# source_eagle.net
KiCad netlist of a schematic drawn in EAGLE
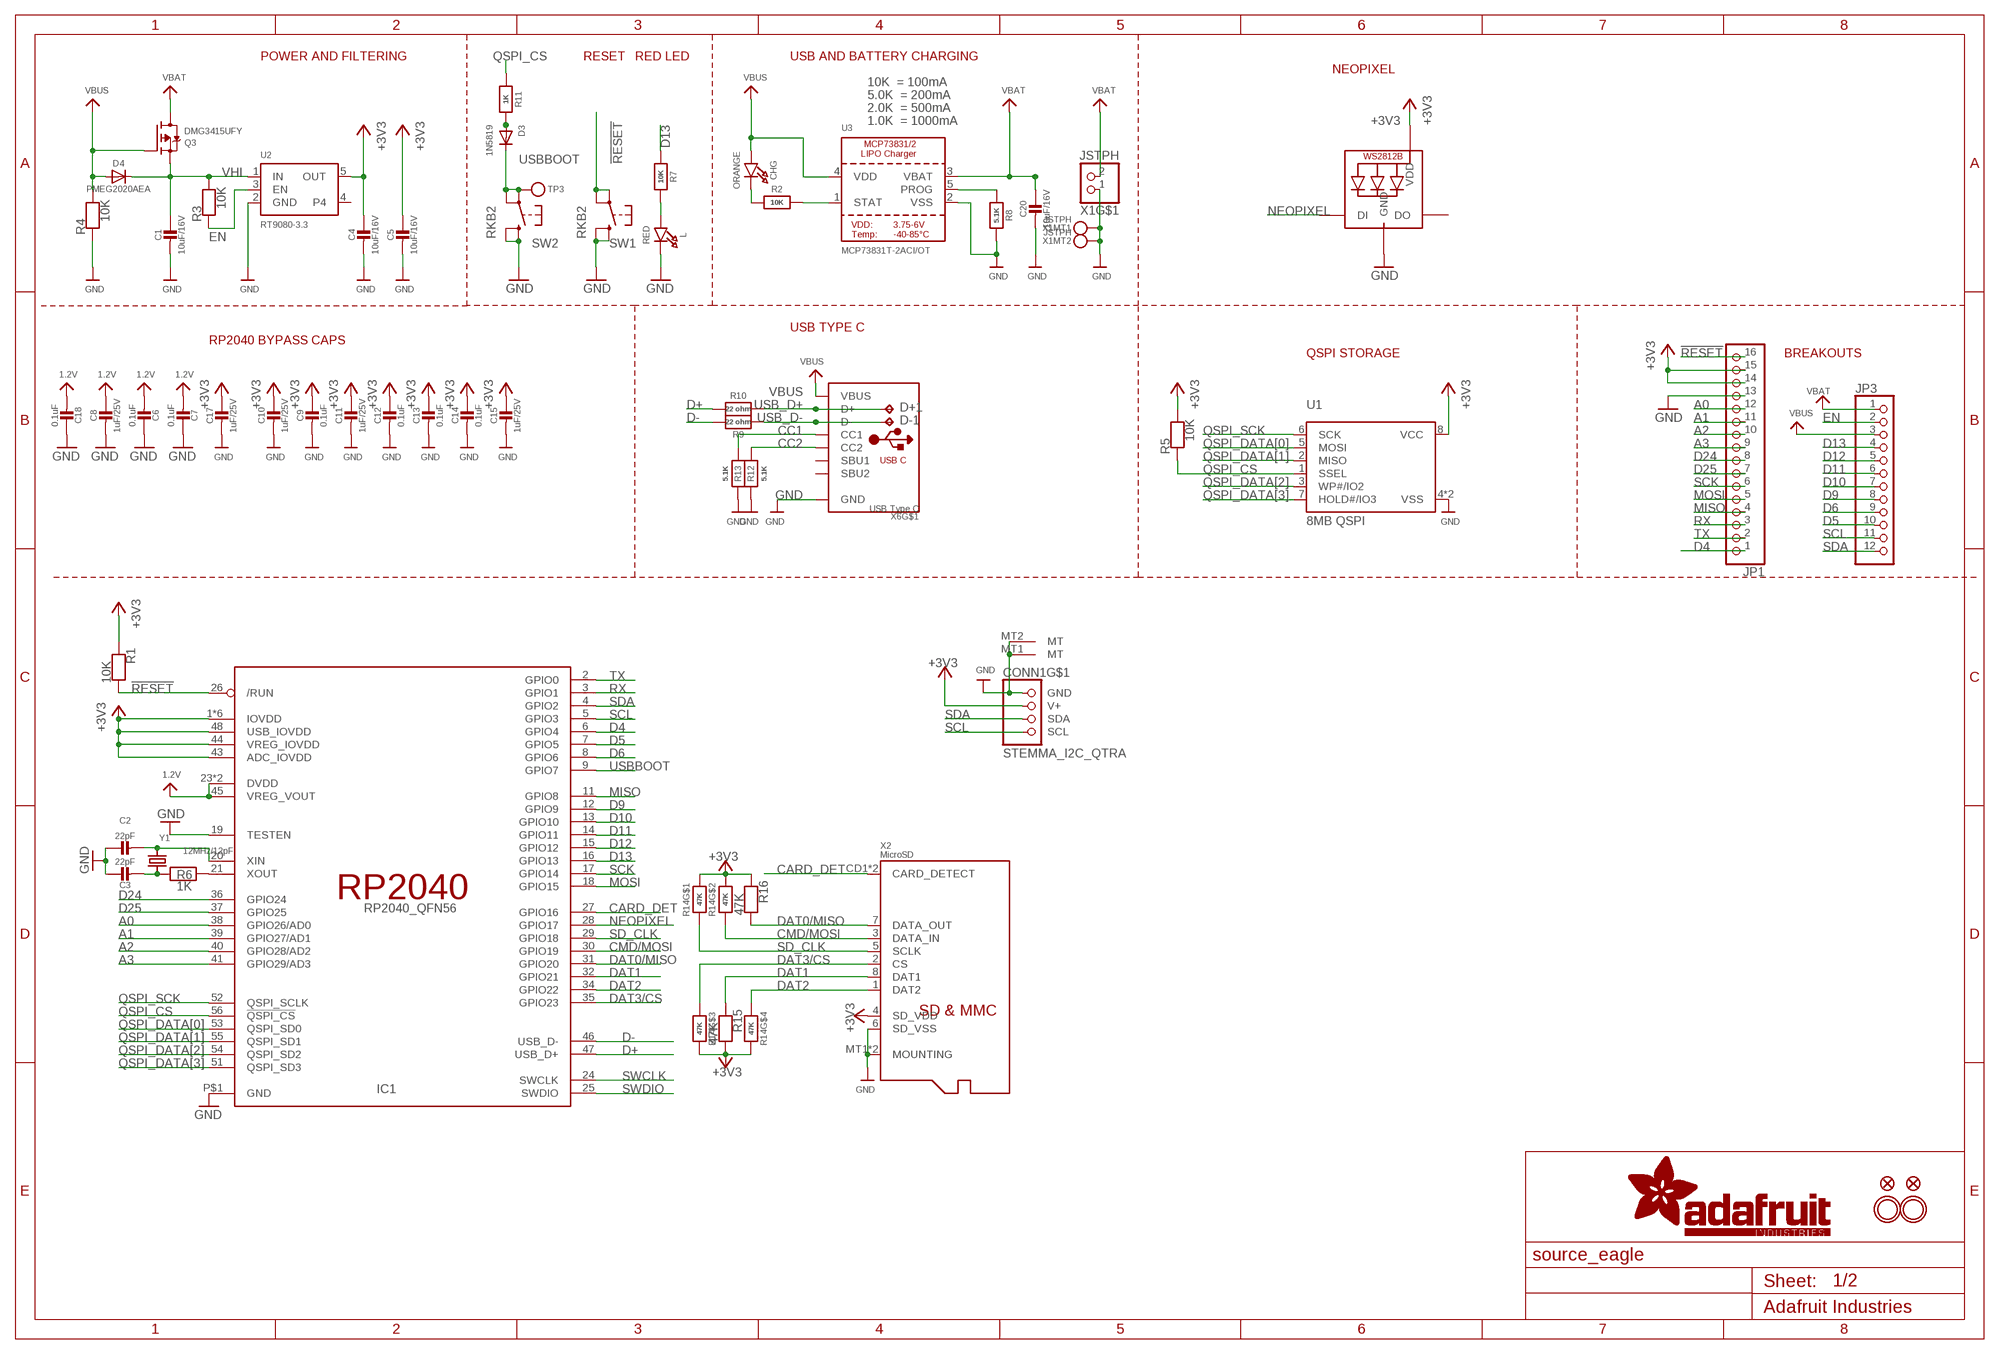
[diagram p0: schematic, sheet 1]

(export (version "E")
  (design (tool "Eeschema 10.0.6"))
  (components
    (comp (ref "C1")
      (value "10uF/16V")
      (footprint "eagle-import:0805-NO")
      (libsource (lib "eagle-import") (part "CAP_CERAMIC0805-NOOUTLINE"))
    )
    (comp (ref "C2")
      (value "22pF")
      (footprint "eagle-import:_0402NO")
      (libsource (lib "eagle-import") (part "CAP_CERAMIC_0402NO"))
    )
    (comp (ref "C3")
      (value "22pF")
      (footprint "eagle-import:_0402NO")
      (libsource (lib "eagle-import") (part "CAP_CERAMIC_0402NO"))
    )
    (comp (ref "C4")
      (value "10uF/16V")
      (footprint "eagle-import:0805-NO")
      (fields (field (name "REV") "A"))
      (libsource (lib "eagle-import") (part "CAP_CERAMIC0805-NOOUTLINE"))
    )
    (comp (ref "C5")
      (value "10uF/16V")
      (footprint "eagle-import:0805-NO")
      (libsource (lib "eagle-import") (part "CAP_CERAMIC0805-NOOUTLINE"))
    )
    (comp (ref "C6")
      (value "0.1uF")
      (footprint "eagle-import:_0402NO")
      (libsource (lib "eagle-import") (part "CAP_CERAMIC_0402NO"))
    )
    (comp (ref "C7")
      (value "0.1uF")
      (footprint "eagle-import:_0402NO")
      (libsource (lib "eagle-import") (part "CAP_CERAMIC_0402NO"))
    )
    (comp (ref "C8")
      (value "1uF/25V")
      (footprint "eagle-import:_0402NO")
      (libsource (lib "eagle-import") (part "CAP_CERAMIC_0402NO"))
    )
    (comp (ref "C9")
      (value "0.1uF")
      (footprint "eagle-import:_0402NO")
      (libsource (lib "eagle-import") (part "CAP_CERAMIC_0402NO"))
    )
    (comp (ref "C10")
      (value "1uF/25V")
      (footprint "eagle-import:_0402NO")
      (libsource (lib "eagle-import") (part "CAP_CERAMIC_0402NO"))
    )
    (comp (ref "C11")
      (value "1uF/25V")
      (footprint "eagle-import:_0402NO")
      (libsource (lib "eagle-import") (part "CAP_CERAMIC_0402NO"))
    )
    (comp (ref "C12")
      (value "0.1uF")
      (footprint "eagle-import:_0402NO")
      (libsource (lib "eagle-import") (part "CAP_CERAMIC_0402NO"))
    )
    (comp (ref "C13")
      (value "0.1uF")
      (footprint "eagle-import:_0402NO")
      (libsource (lib "eagle-import") (part "CAP_CERAMIC_0402NO"))
    )
    (comp (ref "C14")
      (value "0.1uF")
      (footprint "eagle-import:_0402NO")
      (libsource (lib "eagle-import") (part "CAP_CERAMIC_0402NO"))
    )
    (comp (ref "C15")
      (value "1uF/25V")
      (footprint "eagle-import:_0402NO")
      (libsource (lib "eagle-import") (part "CAP_CERAMIC_0402NO"))
    )
    (comp (ref "C17")
      (value "1uF/25V")
      (footprint "eagle-import:_0402NO")
      (libsource (lib "eagle-import") (part "CAP_CERAMIC_0402NO"))
    )
    (comp (ref "C18")
      (value "0.1uF")
      (footprint "eagle-import:_0402NO")
      (libsource (lib "eagle-import") (part "CAP_CERAMIC_0402NO"))
    )
    (comp (ref "C20")
      (value "10uF/16V")
      (footprint "eagle-import:0805-NO")
      (libsource (lib "eagle-import") (part "CAP_CERAMIC0805-NOOUTLINE"))
    )
    (comp (ref "CHG")
      (value "ORANGE")
      (footprint "eagle-import:CHIPLED_0603_NOOUTLINE")
      (libsource (lib "eagle-import") (part "LED0603_NOOUTLINE"))
    )
    (comp (ref "CONN1")
      (value "STEMMA_I2C_QTRA")
      (footprint "eagle-import:JST_SH4_RA")
      (libsource (lib "eagle-import") (part "STEMMA_I2C_QTRA"))
    )
    (comp (ref "D+1")
      (value "TPB1,27")
      (footprint "eagle-import:B1,27")
      (libsource (lib "eagle-import") (part "TPB1,27"))
    )
    (comp (ref "D-1")
      (value "TPB1,27")
      (footprint "eagle-import:B1,27")
      (libsource (lib "eagle-import") (part "TPB1,27"))
    )
    (comp (ref "D3")
      (value "1N5819")
      (footprint "eagle-import:SOD-323_MINI")
      (libsource (lib "eagle-import") (part "DIODE_SOD323MINI"))
    )
    (comp (ref "D4")
      (value "PMEG2020AEA")
      (footprint "eagle-import:SOD-323F")
      (libsource (lib "eagle-import") (part "DIODESOD-323F"))
    )
    (comp (ref "IC1")
      (value "RP2040_QFN56")
      (footprint "eagle-import:QFN56_7MM_REDUCEDEPAD")
      (libsource (lib "eagle-import") (part "RP2040_QFN56"))
    )
    (comp (ref "JP1")
      (value "HEADER-1X16ROUND")
      (footprint "eagle-import:1X16_ROUND")
      (libsource (lib "eagle-import") (part "HEADER-1X16ROUND"))
    )
    (comp (ref "JP3")
      (value "HEADER-1X12")
      (footprint "eagle-import:1X12_ROUND")
      (libsource (lib "eagle-import") (part "HEADER-1X12"))
    )
    (comp (ref "L")
      (value "RED")
      (footprint "eagle-import:CHIPLED_0603_NOOUTLINE")
      (libsource (lib "eagle-import") (part "LED0603_NOOUTLINE"))
    )
    (comp (ref "LED1")
      (value "WS2812B_SK6805_1515")
      (footprint "eagle-import:SK6805_1515")
      (libsource (lib "eagle-import") (part "WS2812B_SK6805_1515"))
    )
    (comp (ref "Q3")
      (value "DMG3415UFY")
      (footprint "eagle-import:DFN2015-3")
      (libsource (lib "eagle-import") (part "MOSFET-P_DFN2015"))
    )
    (comp (ref "R1")
      (value "10K")
      (footprint "eagle-import:_0402NO")
      (libsource (lib "eagle-import") (part "RESISTOR_0402NO"))
    )
    (comp (ref "R2")
      (value "10K")
      (footprint "eagle-import:_0402NO")
      (libsource (lib "eagle-import") (part "RESISTOR_0402NO"))
    )
    (comp (ref "R3")
      (value "10K")
      (footprint "eagle-import:_0402NO")
      (libsource (lib "eagle-import") (part "RESISTOR_0402NO"))
    )
    (comp (ref "R4")
      (value "10K")
      (footprint "eagle-import:_0402NO")
      (libsource (lib "eagle-import") (part "RESISTOR_0402NO"))
    )
    (comp (ref "R5")
      (value "10K")
      (footprint "eagle-import:_0402NO")
      (libsource (lib "eagle-import") (part "RESISTOR_0402NO"))
    )
    (comp (ref "R6")
      (value "1K")
      (footprint "eagle-import:_0402NO")
      (libsource (lib "eagle-import") (part "RESISTOR_0402NO"))
    )
    (comp (ref "R7")
      (value "10K")
      (footprint "eagle-import:_0402NO")
      (libsource (lib "eagle-import") (part "RESISTOR_0402NO"))
    )
    (comp (ref "R8")
      (value "5.1K")
      (footprint "eagle-import:_0402NO")
      (libsource (lib "eagle-import") (part "RESISTOR_0402NO"))
    )
    (comp (ref "R9")
      (value "22 ohm")
      (footprint "eagle-import:_0402NO")
      (libsource (lib "eagle-import") (part "RESISTOR_0402NO"))
    )
    (comp (ref "R10")
      (value "22 ohm")
      (footprint "eagle-import:_0402NO")
      (libsource (lib "eagle-import") (part "RESISTOR_0402NO"))
    )
    (comp (ref "R11")
      (value "1K")
      (footprint "eagle-import:_0402NO")
      (libsource (lib "eagle-import") (part "RESISTOR_0402NO"))
    )
    (comp (ref "R12")
      (value "5.1K")
      (footprint "eagle-import:_0402NO")
      (libsource (lib "eagle-import") (part "RESISTOR_0402NO"))
    )
    (comp (ref "R13")
      (value "5.1K")
      (footprint "eagle-import:_0402NO")
      (libsource (lib "eagle-import") (part "RESISTOR_0402NO"))
    )
    (comp (ref "R14")
      (value "47K")
      (footprint "eagle-import:RESPACK_4X0603")
      (libsource (lib "eagle-import") (part "RESISTOR_4PACK"))
    )
    (comp (ref "R15")
      (value "47K")
      (footprint "eagle-import:_0402NO")
      (libsource (lib "eagle-import") (part "RESISTOR_0402NO"))
    )
    (comp (ref "R16")
      (value "47K")
      (footprint "eagle-import:_0402NO")
      (libsource (lib "eagle-import") (part "RESISTOR_0402NO"))
    )
    (comp (ref "SW1")
      (value "RKB2")
      (footprint "eagle-import:BTN_RKB2_4.6X2.8")
      (libsource (lib "eagle-import") (part "SWITCH_TACT_SMT_RKB2"))
    )
    (comp (ref "SW2")
      (value "RKB2")
      (footprint "eagle-import:BTN_RKB2_4.6X2.8")
      (libsource (lib "eagle-import") (part "SWITCH_TACT_SMT_RKB2"))
    )
    (comp (ref "TP3")
      (value "TESTPOINTROUND1.5MMNO")
      (footprint "eagle-import:TESTPOINT_ROUND_1.5MM_NO")
      (libsource (lib "eagle-import") (part "TESTPOINTROUND1.5MMNO"))
    )
    (comp (ref "U$31")
      (value "MOUNTINGHOLE2.5")
      (footprint "eagle-import:MOUNTINGHOLE_2.5_PLATED")
      (libsource (lib "eagle-import") (part "MOUNTINGHOLE2.5"))
    )
    (comp (ref "U$32")
      (value "MOUNTINGHOLE2.5")
      (footprint "eagle-import:MOUNTINGHOLE_2.5_PLATED")
      (libsource (lib "eagle-import") (part "MOUNTINGHOLE2.5"))
    )
    (comp (ref "U$34")
      (value "FIDUCIAL_1MM")
      (footprint "eagle-import:FIDUCIAL_1MM")
      (libsource (lib "eagle-import") (part "FIDUCIAL_1MM"))
    )
    (comp (ref "U$35")
      (value "FIDUCIAL_1MM")
      (footprint "eagle-import:FIDUCIAL_1MM")
      (libsource (lib "eagle-import") (part "FIDUCIAL_1MM"))
    )
    (comp (ref "U1")
      (value "8MB QSPI")
      (footprint "eagle-import:USON8_4X4")
      (libsource (lib "eagle-import") (part "SPIFLASH_8PIN_4X4"))
    )
    (comp (ref "U2")
      (value "RT9080-3.3")
      (footprint "eagle-import:SOT23-5")
      (fields (field (name "JLC_ROTATION") "0"))
      (libsource (lib "eagle-import") (part "VREG_SOT23-5"))
    )
    (comp (ref "U3")
      (value "MCP73831T-2ACI/OT")
      (footprint "eagle-import:SOT23-5")
      (libsource (lib "eagle-import") (part "MCP73831/2"))
    )
    (comp (ref "X1")
      (value "JSTPH")
      (footprint "eagle-import:JSTPH2_BATT")
      (libsource (lib "eagle-import") (part "CON_JST_PH_2PIN_MT_BATT"))
    )
    (comp (ref "X2")
      (value "MicroSD")
      (footprint "eagle-import:MICROSD")
      (libsource (lib "eagle-import") (part "MICROSD"))
    )
    (comp (ref "X6")
      (value "USB Type C")
      (footprint "eagle-import:USB_C_CUSB31-CFM2AX-01-X")
      (libsource (lib "eagle-import") (part "USB_C"))
    )
    (comp (ref "Y1")
      (value "12MHz/12pF")
      (footprint "eagle-import:CRYSTAL_2.5X2")
      (libsource (lib "eagle-import") (part "CRYSTAL2.5X2.0"))
    )
  )
  (nets
    (net (code "1") (name "+3V3") (class "Default")
      (node (ref "C10") (pin "1") (pinfunction "1_1") (pintype "passive"))
      (node (ref "C11") (pin "1") (pinfunction "1_1") (pintype "passive"))
      (node (ref "C12") (pin "1") (pinfunction "1_1") (pintype "passive"))
      (node (ref "C13") (pin "1") (pinfunction "1_1") (pintype "passive"))
      (node (ref "C14") (pin "1") (pinfunction "1_1") (pintype "passive"))
      (node (ref "C15") (pin "1") (pinfunction "1_1") (pintype "passive"))
      (node (ref "C17") (pin "1") (pinfunction "1_1") (pintype "passive"))
      (node (ref "C4") (pin "1") (pinfunction "1_1") (pintype "passive"))
      (node (ref "C5") (pin "1") (pinfunction "1_1") (pintype "passive"))
      (node (ref "C9") (pin "1") (pinfunction "1_1") (pintype "passive"))
      (node (ref "CONN1") (pin "2") (pinfunction "V+_2") (pintype "passive"))
      (node (ref "IC1") (pin "1") (pinfunction "IOVDD_1") (pintype "power_in"))
      (node (ref "IC1") (pin "10") (pinfunction "IOVDD_10") (pintype "power_in"))
      (node (ref "IC1") (pin "22") (pinfunction "IOVDD_22") (pintype "power_in"))
      (node (ref "IC1") (pin "33") (pinfunction "IOVDD_33") (pintype "power_in"))
      (node (ref "IC1") (pin "42") (pinfunction "IOVDD_42") (pintype "power_in"))
      (node (ref "IC1") (pin "43") (pinfunction "ADC_IOVDD_43") (pintype "power_in"))
      (node (ref "IC1") (pin "44") (pinfunction "VREG_IOVDD_44") (pintype "power_in"))
      (node (ref "IC1") (pin "48") (pinfunction "USB_IOVDD_48") (pintype "power_in"))
      (node (ref "IC1") (pin "49") (pinfunction "IOVDD_49") (pintype "power_in"))
      (node (ref "JP1") (pin "14") (pinfunction "14_14") (pintype "passive"))
      (node (ref "JP1") (pin "15") (pinfunction "15_15") (pintype "passive"))
      (node (ref "LED1") (pin "2") (pinfunction "VDD_2") (pintype "power_in"))
      (node (ref "R1") (pin "1") (pinfunction "1_1") (pintype "passive"))
      (node (ref "R14") (pin "5") (pinfunction "2_5") (pintype "passive"))
      (node (ref "R14") (pin "6") (pinfunction "2_6") (pintype "passive"))
      (node (ref "R14") (pin "7") (pinfunction "2_7") (pintype "passive"))
      (node (ref "R14") (pin "8") (pinfunction "2_8") (pintype "passive"))
      (node (ref "R15") (pin "2") (pinfunction "2_2") (pintype "passive"))
      (node (ref "R16") (pin "1") (pinfunction "1_1") (pintype "passive"))
      (node (ref "R5") (pin "2") (pinfunction "2_2") (pintype "passive"))
      (node (ref "U1") (pin "8") (pinfunction "VCC_8") (pintype "bidirectional"))
      (node (ref "U2") (pin "5") (pinfunction "OUT_5") (pintype "power_in"))
      (node (ref "X2") (pin "4") (pinfunction "SD_VDD_4") (pintype "power_in"))
    )
    (net (code "2") (name "1.2V") (class "Default")
      (node (ref "C18") (pin "2") (pinfunction "2_2") (pintype "passive"))
      (node (ref "C6") (pin "2") (pinfunction "2_2") (pintype "passive"))
      (node (ref "C7") (pin "2") (pinfunction "2_2") (pintype "passive"))
      (node (ref "C8") (pin "1") (pinfunction "1_1") (pintype "passive"))
      (node (ref "IC1") (pin "23") (pinfunction "DVDD_23") (pintype "power_in"))
      (node (ref "IC1") (pin "45") (pinfunction "VREG_VOUT_45") (pintype "power_in"))
      (node (ref "IC1") (pin "50") (pinfunction "DVDD_50") (pintype "power_in"))
    )
    (net (code "3") (name "A0") (class "Default")
      (node (ref "IC1") (pin "38") (pinfunction "GPIO26/AD0_38") (pintype "bidirectional"))
      (node (ref "JP1") (pin "12") (pinfunction "12_12") (pintype "passive"))
    )
    (net (code "4") (name "A1") (class "Default")
      (node (ref "IC1") (pin "39") (pinfunction "GPIO27/AD1_39") (pintype "bidirectional"))
      (node (ref "JP1") (pin "11") (pinfunction "11_11") (pintype "passive"))
    )
    (net (code "5") (name "A2") (class "Default")
      (node (ref "IC1") (pin "40") (pinfunction "GPIO28/AD2_40") (pintype "bidirectional"))
      (node (ref "JP1") (pin "10") (pinfunction "10_10") (pintype "passive"))
    )
    (net (code "6") (name "A3") (class "Default")
      (node (ref "IC1") (pin "41") (pinfunction "GPIO29/AD3_41") (pintype "bidirectional"))
      (node (ref "JP1") (pin "9") (pinfunction "9_9") (pintype "passive"))
    )
    (net (code "7") (name "CARD_DET") (class "Default")
      (node (ref "IC1") (pin "27") (pinfunction "GPIO16_27") (pintype "bidirectional"))
      (node (ref "X2") (pin "CD1") (pinfunction "CARD_DETECT_CD1") (pintype "passive"))
      (node (ref "X2") (pin "CD2") (pinfunction "CARD_DETECT_CD2") (pintype "passive"))
    )
    (net (code "8") (name "CC1") (class "Default")
      (node (ref "R13") (pin "2") (pinfunction "2_2") (pintype "passive"))
      (node (ref "X6") (pin "A5") (pinfunction "CC1_A5") (pintype "bidirectional"))
    )
    (net (code "9") (name "CC2") (class "Default")
      (node (ref "R12") (pin "2") (pinfunction "2_2") (pintype "passive"))
      (node (ref "X6") (pin "B5") (pinfunction "CC2_B5") (pintype "bidirectional"))
    )
    (net (code "10") (name "CMD{slash}MOSI") (class "Default")
      (node (ref "IC1") (pin "30") (pinfunction "GPIO19_30") (pintype "bidirectional"))
      (node (ref "R14") (pin "2") (pinfunction "1_2") (pintype "passive"))
      (node (ref "X2") (pin "3") (pinfunction "DATA_IN_3") (pintype "input"))
    )
    (net (code "11") (name "D+") (class "Default")
      (node (ref "IC1") (pin "47") (pinfunction "USB_D+_47") (pintype "bidirectional"))
      (node (ref "R10") (pin "2") (pinfunction "2_2") (pintype "passive"))
    )
    (net (code "12") (name "D-") (class "Default")
      (node (ref "IC1") (pin "46") (pinfunction "USB_D-_46") (pintype "bidirectional"))
      (node (ref "R9") (pin "2") (pinfunction "2_2") (pintype "passive"))
    )
    (net (code "13") (name "D4") (class "Default")
      (node (ref "IC1") (pin "6") (pinfunction "GPIO4_6") (pintype "bidirectional"))
      (node (ref "JP1") (pin "1") (pinfunction "1_1") (pintype "passive"))
    )
    (net (code "14") (name "D5") (class "Default")
      (node (ref "IC1") (pin "7") (pinfunction "GPIO5_7") (pintype "bidirectional"))
      (node (ref "JP3") (pin "10") (pinfunction "10_10") (pintype "passive"))
    )
    (net (code "15") (name "D6") (class "Default")
      (node (ref "IC1") (pin "8") (pinfunction "GPIO6_8") (pintype "bidirectional"))
      (node (ref "JP3") (pin "9") (pinfunction "9_9") (pintype "passive"))
    )
    (net (code "16") (name "D9") (class "Default")
      (node (ref "IC1") (pin "12") (pinfunction "GPIO9_12") (pintype "bidirectional"))
      (node (ref "JP3") (pin "8") (pinfunction "8_8") (pintype "passive"))
    )
    (net (code "17") (name "D10") (class "Default")
      (node (ref "IC1") (pin "13") (pinfunction "GPIO10_13") (pintype "bidirectional"))
      (node (ref "JP3") (pin "7") (pinfunction "7_7") (pintype "passive"))
    )
    (net (code "18") (name "D11") (class "Default")
      (node (ref "IC1") (pin "14") (pinfunction "GPIO11_14") (pintype "bidirectional"))
      (node (ref "JP3") (pin "6") (pinfunction "6_6") (pintype "passive"))
    )
    (net (code "19") (name "D12") (class "Default")
      (node (ref "IC1") (pin "15") (pinfunction "GPIO12_15") (pintype "bidirectional"))
      (node (ref "JP3") (pin "5") (pinfunction "5_5") (pintype "passive"))
    )
    (net (code "20") (name "D13") (class "Default")
      (node (ref "IC1") (pin "16") (pinfunction "GPIO13_16") (pintype "bidirectional"))
      (node (ref "JP3") (pin "4") (pinfunction "4_4") (pintype "passive"))
      (node (ref "R7") (pin "1") (pinfunction "1_1") (pintype "passive"))
    )
    (net (code "21") (name "D24") (class "Default")
      (node (ref "IC1") (pin "36") (pinfunction "GPIO24_36") (pintype "bidirectional"))
      (node (ref "JP1") (pin "8") (pinfunction "8_8") (pintype "passive"))
    )
    (net (code "22") (name "D25") (class "Default")
      (node (ref "IC1") (pin "37") (pinfunction "GPIO25_37") (pintype "bidirectional"))
      (node (ref "JP1") (pin "7") (pinfunction "7_7") (pintype "passive"))
    )
    (net (code "23") (name "DAT0{slash}MISO") (class "Default")
      (node (ref "IC1") (pin "31") (pinfunction "GPIO20_31") (pintype "bidirectional"))
      (node (ref "R16") (pin "2") (pinfunction "2_2") (pintype "passive"))
      (node (ref "X2") (pin "7") (pinfunction "DATA_OUT_7") (pintype "output"))
    )
    (net (code "24") (name "DAT1") (class "Default")
      (node (ref "IC1") (pin "32") (pinfunction "GPIO21_32") (pintype "bidirectional"))
      (node (ref "R15") (pin "1") (pinfunction "1_1") (pintype "passive"))
      (node (ref "X2") (pin "8") (pinfunction "DAT1_8") (pintype "bidirectional"))
    )
    (net (code "25") (name "DAT2") (class "Default")
      (node (ref "IC1") (pin "34") (pinfunction "GPIO22_34") (pintype "bidirectional"))
      (node (ref "R14") (pin "4") (pinfunction "1_4") (pintype "passive"))
      (node (ref "X2") (pin "1") (pinfunction "DAT2_1") (pintype "bidirectional"))
    )
    (net (code "26") (name "DAT3{slash}CS") (class "Default")
      (node (ref "IC1") (pin "35") (pinfunction "GPIO23_35") (pintype "bidirectional"))
      (node (ref "R14") (pin "3") (pinfunction "1_3") (pintype "passive"))
      (node (ref "X2") (pin "2") (pinfunction "CS_2") (pintype "input"))
    )
    (net (code "27") (name "EN") (class "Default")
      (node (ref "JP3") (pin "2") (pinfunction "2_2") (pintype "passive"))
      (node (ref "R3") (pin "1") (pinfunction "1_1") (pintype "passive"))
      (node (ref "U2") (pin "3") (pinfunction "EN_3") (pintype "input"))
    )
    (net (code "28") (name "GND") (class "Default")
      (node (ref "C1") (pin "2") (pinfunction "2_2") (pintype "passive"))
      (node (ref "C10") (pin "2") (pinfunction "2_2") (pintype "passive"))
      (node (ref "C11") (pin "2") (pinfunction "2_2") (pintype "passive"))
      (node (ref "C12") (pin "2") (pinfunction "2_2") (pintype "passive"))
      (node (ref "C13") (pin "2") (pinfunction "2_2") (pintype "passive"))
      (node (ref "C14") (pin "2") (pinfunction "2_2") (pintype "passive"))
      (node (ref "C15") (pin "2") (pinfunction "2_2") (pintype "passive"))
      (node (ref "C17") (pin "2") (pinfunction "2_2") (pintype "passive"))
      (node (ref "C18") (pin "1") (pinfunction "1_1") (pintype "passive"))
      (node (ref "C2") (pin "1") (pinfunction "1_1") (pintype "passive"))
      (node (ref "C20") (pin "2") (pinfunction "2_2") (pintype "passive"))
      (node (ref "C3") (pin "1") (pinfunction "1_1") (pintype "passive"))
      (node (ref "C4") (pin "2") (pinfunction "2_2") (pintype "passive"))
      (node (ref "C5") (pin "2") (pinfunction "2_2") (pintype "passive"))
      (node (ref "C6") (pin "1") (pinfunction "1_1") (pintype "passive"))
      (node (ref "C7") (pin "1") (pinfunction "1_1") (pintype "passive"))
      (node (ref "C8") (pin "2") (pinfunction "2_2") (pintype "passive"))
      (node (ref "C9") (pin "2") (pinfunction "2_2") (pintype "passive"))
      (node (ref "CONN1") (pin "1") (pinfunction "GND_1") (pintype "passive"))
      (node (ref "CONN1") (pin "MT1") (pinfunction "MT_MT1") (pintype "bidirectional"))
      (node (ref "CONN1") (pin "MT2") (pinfunction "MT_MT2") (pintype "bidirectional"))
      (node (ref "IC1") (pin "19") (pinfunction "TESTEN_19") (pintype "input"))
      (node (ref "IC1") (pin "P$1") (pinfunction "GND_P$1") (pintype "power_in"))
      (node (ref "JP1") (pin "13") (pinfunction "13_13") (pintype "passive"))
      (node (ref "L") (pin "C") (pinfunction "C_C") (pintype "passive"))
      (node (ref "LED1") (pin "4") (pinfunction "GND_4") (pintype "power_in"))
      (node (ref "R12") (pin "1") (pinfunction "1_1") (pintype "passive"))
      (node (ref "R13") (pin "1") (pinfunction "1_1") (pintype "passive"))
      (node (ref "R4") (pin "1") (pinfunction "1_1") (pintype "passive"))
      (node (ref "R8") (pin "2") (pinfunction "2_2") (pintype "passive"))
      (node (ref "SW1") (pin "B") (pinfunction "S_B") (pintype "passive"))
      (node (ref "SW1") (pin "B'") (pinfunction "S1_B'") (pintype "passive"))
      (node (ref "SW2") (pin "B") (pinfunction "S_B") (pintype "passive"))
      (node (ref "SW2") (pin "B'") (pinfunction "S1_B'") (pintype "passive"))
      (node (ref "U1") (pin "4") (pinfunction "VSS_4") (pintype "bidirectional"))
      (node (ref "U1") (pin "PAD") (pinfunction "VSS_PAD") (pintype "bidirectional"))
      (node (ref "U2") (pin "2") (pinfunction "GND_2") (pintype "power_in"))
      (node (ref "U3") (pin "2") (pinfunction "VSS_2") (pintype "power_in"))
      (node (ref "X1") (pin "1") (pinfunction "1_1") (pintype "passive"))
      (node (ref "X1") (pin "NC1") (pinfunction "P$1_NC1") (pintype "bidirectional"))
      (node (ref "X1") (pin "NC2") (pinfunction "P$1_NC2") (pintype "bidirectional"))
      (node (ref "X2") (pin "6") (pinfunction "SD_VSS_6") (pintype "power_in"))
      (node (ref "X2") (pin "MT1") (pinfunction "MOUNTING_MT1") (pintype "passive"))
      (node (ref "X2") (pin "MT2") (pinfunction "MOUNTING_MT2") (pintype "passive"))
      (node (ref "X6") (pin "A1B12") (pinfunction "GND_A1B12") (pintype "power_in"))
      (node (ref "X6") (pin "B1A12") (pinfunction "GND_B1A12") (pintype "power_in"))
    )
    (net (code "29") (name "MISO") (class "Default")
      (node (ref "IC1") (pin "11") (pinfunction "GPIO8_11") (pintype "bidirectional"))
      (node (ref "JP1") (pin "4") (pinfunction "4_4") (pintype "passive"))
    )
    (net (code "30") (name "MOSI") (class "Default")
      (node (ref "IC1") (pin "18") (pinfunction "GPIO15_18") (pintype "bidirectional"))
      (node (ref "JP1") (pin "5") (pinfunction "5_5") (pintype "passive"))
    )
    (net (code "31") (name "NEOPIXEL") (class "Default")
      (node (ref "IC1") (pin "28") (pinfunction "GPIO17_28") (pintype "bidirectional"))
      (node (ref "LED1") (pin "1") (pinfunction "DI_1") (pintype "input"))
    )
    (net (code "32") (name "Net-(C3-Pad2)") (class "Default")
      (node (ref "C3") (pin "2") (pinfunction "2_2") (pintype "passive"))
      (node (ref "R6") (pin "1") (pinfunction "1_1") (pintype "passive"))
      (node (ref "Y1") (pin "1") (pinfunction "1_1") (pintype "passive"))
    )
    (net (code "33") (name "Net-(CHG-PadC)") (class "Default")
      (node (ref "CHG") (pin "C") (pinfunction "C_C") (pintype "passive"))
      (node (ref "R2") (pin "1") (pinfunction "1_1") (pintype "passive"))
    )
    (net (code "34") (name "Net-(D3-PadA)") (class "Default")
      (node (ref "D3") (pin "A") (pinfunction "A_A") (pintype "passive"))
      (node (ref "R11") (pin "2") (pinfunction "2_2") (pintype "passive"))
    )
    (net (code "35") (name "Net-(IC1-XIN)") (class "Default")
      (node (ref "C2") (pin "2") (pinfunction "2_2") (pintype "passive"))
      (node (ref "IC1") (pin "20") (pinfunction "XIN_20") (pintype "input"))
      (node (ref "Y1") (pin "3") (pinfunction "2_3") (pintype "passive"))
    )
    (net (code "36") (name "Net-(IC1-XOUT)") (class "Default")
      (node (ref "IC1") (pin "21") (pinfunction "XOUT_21") (pintype "output"))
      (node (ref "R6") (pin "2") (pinfunction "2_2") (pintype "passive"))
    )
    (net (code "37") (name "Net-(L-PadA)") (class "Default")
      (node (ref "L") (pin "A") (pinfunction "A_A") (pintype "passive"))
      (node (ref "R7") (pin "2") (pinfunction "2_2") (pintype "passive"))
    )
    (net (code "38") (name "Net-(U3-PROG)") (class "Default")
      (node (ref "R8") (pin "1") (pinfunction "1_1") (pintype "passive"))
      (node (ref "U3") (pin "5") (pinfunction "PROG_5") (pintype "input"))
    )
    (net (code "39") (name "Net-(U3-STAT)") (class "Default")
      (node (ref "R2") (pin "2") (pinfunction "2_2") (pintype "passive"))
      (node (ref "U3") (pin "1") (pinfunction "STAT_1") (pintype "output"))
    )
    (net (code "40") (name "QSPI_CS") (class "Default")
      (node (ref "IC1") (pin "56") (pinfunction "~{QSPI_CS}_56") (pintype "bidirectional"))
      (node (ref "R11") (pin "1") (pinfunction "1_1") (pintype "passive"))
      (node (ref "R5") (pin "1") (pinfunction "1_1") (pintype "passive"))
      (node (ref "U1") (pin "1") (pinfunction "SSEL_1") (pintype "bidirectional"))
    )
    (net (code "41") (name "QSPI_DATA[0]") (class "Default")
      (node (ref "IC1") (pin "53") (pinfunction "QSPI_SD0_53") (pintype "bidirectional"))
      (node (ref "U1") (pin "5") (pinfunction "MOSI_5") (pintype "bidirectional"))
    )
    (net (code "42") (name "QSPI_DATA[1]") (class "Default")
      (node (ref "IC1") (pin "55") (pinfunction "QSPI_SD1_55") (pintype "bidirectional"))
      (node (ref "U1") (pin "2") (pinfunction "MISO_2") (pintype "bidirectional"))
    )
    (net (code "43") (name "QSPI_DATA[2]") (class "Default")
      (node (ref "IC1") (pin "54") (pinfunction "QSPI_SD2_54") (pintype "bidirectional"))
      (node (ref "U1") (pin "3") (pinfunction "WP#/IO2_3") (pintype "bidirectional"))
    )
    (net (code "44") (name "QSPI_DATA[3]") (class "Default")
      (node (ref "IC1") (pin "51") (pinfunction "QSPI_SD3_51") (pintype "bidirectional"))
      (node (ref "U1") (pin "7") (pinfunction "HOLD#/IO3_7") (pintype "bidirectional"))
    )
    (net (code "45") (name "QSPI_SCK") (class "Default")
      (node (ref "IC1") (pin "52") (pinfunction "QSPI_SCLK_52") (pintype "bidirectional"))
      (node (ref "U1") (pin "6") (pinfunction "SCK_6") (pintype "bidirectional"))
    )
    (net (code "46") (name "RX") (class "Default")
      (node (ref "IC1") (pin "3") (pinfunction "GPIO1_3") (pintype "bidirectional"))
      (node (ref "JP1") (pin "3") (pinfunction "3_3") (pintype "passive"))
    )
    (net (code "47") (name "SCK") (class "Default")
      (node (ref "IC1") (pin "17") (pinfunction "GPIO14_17") (pintype "bidirectional"))
      (node (ref "JP1") (pin "6") (pinfunction "6_6") (pintype "passive"))
    )
    (net (code "48") (name "SCL") (class "Default")
      (node (ref "CONN1") (pin "4") (pinfunction "SCL_4") (pintype "passive"))
      (node (ref "IC1") (pin "5") (pinfunction "GPIO3_5") (pintype "bidirectional"))
      (node (ref "JP3") (pin "11") (pinfunction "11_11") (pintype "passive"))
    )
    (net (code "49") (name "SDA") (class "Default")
      (node (ref "CONN1") (pin "3") (pinfunction "SDA_3") (pintype "passive"))
      (node (ref "IC1") (pin "4") (pinfunction "GPIO2_4") (pintype "bidirectional"))
      (node (ref "JP3") (pin "12") (pinfunction "12_12") (pintype "passive"))
    )
    (net (code "50") (name "SD_CLK") (class "Default")
      (node (ref "IC1") (pin "29") (pinfunction "GPIO18_29") (pintype "bidirectional"))
      (node (ref "R14") (pin "1") (pinfunction "1_1") (pintype "passive"))
      (node (ref "X2") (pin "5") (pinfunction "SCLK_5") (pintype "input"))
    )
    (net (code "51") (name "SWCLK") (class "Default")
      (node (ref "IC1") (pin "24") (pinfunction "SWCLK_24") (pintype "bidirectional"))
    )
    (net (code "52") (name "SWDIO") (class "Default")
      (node (ref "IC1") (pin "25") (pinfunction "SWDIO_25") (pintype "bidirectional"))
    )
    (net (code "53") (name "TX") (class "Default")
      (node (ref "IC1") (pin "2") (pinfunction "GPIO0_2") (pintype "bidirectional"))
      (node (ref "JP1") (pin "2") (pinfunction "2_2") (pintype "passive"))
    )
    (net (code "54") (name "USBBOOT") (class "Default")
      (node (ref "D3") (pin "C") (pinfunction "C_C") (pintype "passive"))
      (node (ref "IC1") (pin "9") (pinfunction "GPIO7_9") (pintype "bidirectional"))
      (node (ref "SW2") (pin "A") (pinfunction "P_A") (pintype "passive"))
      (node (ref "SW2") (pin "A'") (pinfunction "P1_A'") (pintype "passive"))
      (node (ref "TP3") (pin "P$1") (pinfunction "P$1_P$1") (pintype "bidirectional"))
    )
    (net (code "55") (name "USB_D+") (class "Default")
      (node (ref "D+1") (pin "TP") (pinfunction "TP_TP") (pintype "input"))
      (node (ref "R10") (pin "1") (pinfunction "1_1") (pintype "passive"))
      (node (ref "X6") (pin "A6") (pinfunction "D+_A6") (pintype "bidirectional"))
      (node (ref "X6") (pin "B6") (pinfunction "D+_B6") (pintype "bidirectional"))
    )
    (net (code "56") (name "USB_D-") (class "Default")
      (node (ref "D-1") (pin "TP") (pinfunction "TP_TP") (pintype "input"))
      (node (ref "R9") (pin "1") (pinfunction "1_1") (pintype "passive"))
      (node (ref "X6") (pin "A7") (pinfunction "D-_A7") (pintype "bidirectional"))
      (node (ref "X6") (pin "B7") (pinfunction "D-_B7") (pintype "bidirectional"))
    )
    (net (code "57") (name "VBAT") (class "Default")
      (node (ref "C20") (pin "1") (pinfunction "1_1") (pintype "passive"))
      (node (ref "JP3") (pin "1") (pinfunction "1_1") (pintype "passive"))
      (node (ref "Q3") (pin "3") (pinfunction "D_3") (pintype "passive"))
      (node (ref "U3") (pin "3") (pinfunction "VBAT_3") (pintype "power_in"))
      (node (ref "X1") (pin "2") (pinfunction "2_2") (pintype "passive"))
    )
    (net (code "58") (name "VBUS") (class "Default")
      (node (ref "CHG") (pin "A") (pinfunction "A_A") (pintype "passive"))
      (node (ref "D4") (pin "A") (pinfunction "A_A") (pintype "passive"))
      (node (ref "JP3") (pin "3") (pinfunction "3_3") (pintype "passive"))
      (node (ref "Q3") (pin "1") (pinfunction "G_1") (pintype "passive"))
      (node (ref "R4") (pin "2") (pinfunction "2_2") (pintype "passive"))
      (node (ref "U3") (pin "4") (pinfunction "VDD_4") (pintype "power_in"))
      (node (ref "X6") (pin "A4B9") (pinfunction "VBUS_A4B9") (pintype "power_in"))
      (node (ref "X6") (pin "B4A9") (pinfunction "VBUS_B4A9") (pintype "power_in"))
    )
    (net (code "59") (name "VHI") (class "Default")
      (node (ref "C1") (pin "1") (pinfunction "1_1") (pintype "passive"))
      (node (ref "D4") (pin "C") (pinfunction "C_C") (pintype "passive"))
      (node (ref "Q3") (pin "2") (pinfunction "S_2") (pintype "passive"))
      (node (ref "R3") (pin "2") (pinfunction "2_2") (pintype "passive"))
      (node (ref "U2") (pin "1") (pinfunction "IN_1") (pintype "power_in"))
    )
    (net (code "60") (name "unconnected-(LED1-DO-Pad3)") (class "Default")
      (node (ref "LED1") (pin "3") (pinfunction "DO_3") (pintype "output"))
    )
    (net (code "61") (name "unconnected-(U2-P4-Pad4)") (class "Default")
      (node (ref "U2") (pin "4") (pinfunction "P4_4") (pintype "bidirectional"))
    )
    (net (code "62") (name "unconnected-(X6A-SBU1-PadA8)") (class "Default")
      (node (ref "X6") (pin "A8") (pinfunction "SBU1_A8") (pintype "bidirectional"))
    )
    (net (code "63") (name "unconnected-(X6A-SBU2-PadB8)") (class "Default")
      (node (ref "X6") (pin "B8") (pinfunction "SBU2_B8") (pintype "bidirectional"))
    )
    (net (code "64") (name "~{RESET}") (class "Default")
      (node (ref "IC1") (pin "26") (pinfunction "/RUN_26") (pintype "bidirectional"))
      (node (ref "JP1") (pin "16") (pinfunction "16_16") (pintype "passive"))
      (node (ref "R1") (pin "2") (pinfunction "2_2") (pintype "passive"))
      (node (ref "SW1") (pin "A") (pinfunction "P_A") (pintype "passive"))
      (node (ref "SW1") (pin "A'") (pinfunction "P1_A'") (pintype "passive"))
    )
  )
)
